# tricoreVCO.net
KiCad netlist of a schematic drawn in EAGLE
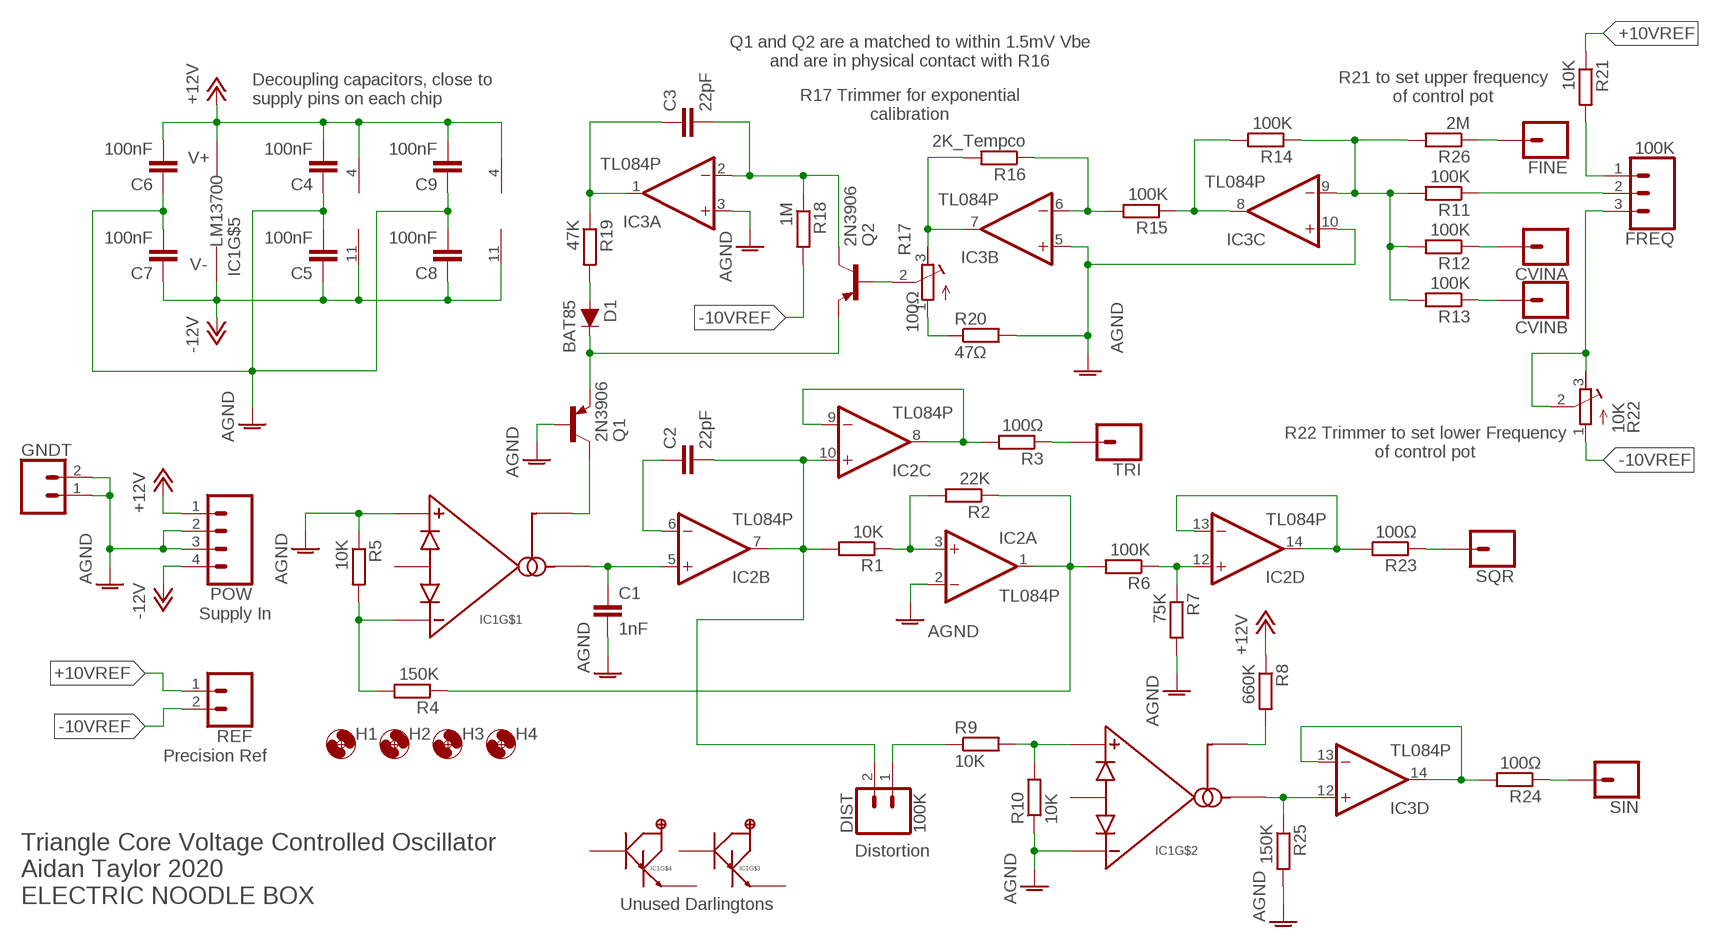
[diagram p0: schematic, sheet 1]

(export (version "E")
  (design (tool "Eeschema 10.0.6"))
  (components
    (comp (ref "C1")
      (value "1nF")
      (footprint "eagle-import:C050-025X075")
      (libsource (lib "eagle-import") (part "C-EU050-025X075"))
    )
    (comp (ref "C2")
      (value "22pF")
      (footprint "eagle-import:C050-025X075")
      (libsource (lib "eagle-import") (part "C-EU050-025X075"))
    )
    (comp (ref "C3")
      (value "22pF")
      (footprint "eagle-import:C050-025X075")
      (libsource (lib "eagle-import") (part "C-EU050-025X075"))
    )
    (comp (ref "C4")
      (value "100nF")
      (footprint "eagle-import:C050-025X075")
      (libsource (lib "eagle-import") (part "C-EU050-025X075"))
    )
    (comp (ref "C5")
      (value "100nF")
      (footprint "eagle-import:C050-025X075")
      (libsource (lib "eagle-import") (part "C-EU050-025X075"))
    )
    (comp (ref "C6")
      (value "100nF")
      (footprint "eagle-import:C050-025X075")
      (libsource (lib "eagle-import") (part "C-EU050-025X075"))
    )
    (comp (ref "C7")
      (value "100nF")
      (footprint "eagle-import:C050-025X075")
      (libsource (lib "eagle-import") (part "C-EU050-025X075"))
    )
    (comp (ref "C8")
      (value "100nF")
      (footprint "eagle-import:C050-025X075")
      (libsource (lib "eagle-import") (part "C-EU050-025X075"))
    )
    (comp (ref "C9")
      (value "100nF")
      (footprint "eagle-import:C050-025X075")
      (libsource (lib "eagle-import") (part "C-EU050-025X075"))
    )
    (comp (ref "CVINA")
      (value "CONN_01")
      (footprint "eagle-import:1X01")
      (libsource (lib "eagle-import") (part "CONN_01"))
    )
    (comp (ref "CVINB")
      (value "CONN_01")
      (footprint "eagle-import:1X01")
      (libsource (lib "eagle-import") (part "CONN_01"))
    )
    (comp (ref "D1")
      (value "BAT85")
      (footprint "eagle-import:DIODE-1N4148")
      (libsource (lib "eagle-import") (part "DIODE-1N4148"))
    )
    (comp (ref "DIST")
      (value "100K")
      (footprint "eagle-import:1X02")
      (libsource (lib "eagle-import") (part "CONN_02"))
    )
    (comp (ref "FINE")
      (value "CONN_01")
      (footprint "eagle-import:1X01")
      (libsource (lib "eagle-import") (part "CONN_01"))
    )
    (comp (ref "FREQ")
      (value "100K")
      (footprint "eagle-import:1X03")
      (libsource (lib "eagle-import") (part "CONN_03"))
    )
    (comp (ref "GNDT")
      (value "CONN_02")
      (footprint "eagle-import:1X02")
      (libsource (lib "eagle-import") (part "CONN_02"))
    )
    (comp (ref "H1")
      (value "MOUNT-HOLE3.2")
      (footprint "eagle-import:3,2")
      (libsource (lib "eagle-import") (part "MOUNT-HOLE3.2"))
    )
    (comp (ref "H2")
      (value "MOUNT-HOLE3.2")
      (footprint "eagle-import:3,2")
      (libsource (lib "eagle-import") (part "MOUNT-HOLE3.2"))
    )
    (comp (ref "H3")
      (value "MOUNT-HOLE3.2")
      (footprint "eagle-import:3,2")
      (libsource (lib "eagle-import") (part "MOUNT-HOLE3.2"))
    )
    (comp (ref "H4")
      (value "MOUNT-HOLE3.2")
      (footprint "eagle-import:3,2")
      (libsource (lib "eagle-import") (part "MOUNT-HOLE3.2"))
    )
    (comp (ref "IC1")
      (value "LM13700_DIP")
      (footprint "eagle-import:DIP16")
      (libsource (lib "eagle-import") (part "LM13700_DIP"))
    )
    (comp (ref "IC2")
      (value "TL084P")
      (footprint "eagle-import:DIL14")
      (libsource (lib "eagle-import") (part "TL084P"))
    )
    (comp (ref "IC3")
      (value "TL084P")
      (footprint "eagle-import:DIL14")
      (libsource (lib "eagle-import") (part "TL084P"))
    )
    (comp (ref "POW")
      (value "CONN_04POLAR")
      (footprint "eagle-import:MOLEX-1X4")
      (libsource (lib "eagle-import") (part "CONN_04POLAR"))
    )
    (comp (ref "Q1")
      (value "2N3906")
      (footprint "eagle-import:TO92")
      (libsource (lib "eagle-import") (part "2N3906"))
    )
    (comp (ref "Q2")
      (value "2N3906")
      (footprint "eagle-import:TO92")
      (libsource (lib "eagle-import") (part "2N3906"))
    )
    (comp (ref "R1")
      (value "10K")
      (footprint "eagle-import:0207_10")
      (libsource (lib "eagle-import") (part "R-EU_0207/10"))
    )
    (comp (ref "R2")
      (value "22K")
      (footprint "eagle-import:0207_10")
      (libsource (lib "eagle-import") (part "R-EU_0207/10"))
    )
    (comp (ref "R3")
      (value "100Ω")
      (footprint "eagle-import:0207_10")
      (libsource (lib "eagle-import") (part "R-EU_0207/10"))
    )
    (comp (ref "R4")
      (value "150K")
      (footprint "eagle-import:0207_10")
      (libsource (lib "eagle-import") (part "R-EU_0207/10"))
    )
    (comp (ref "R5")
      (value "10K")
      (footprint "eagle-import:0207_10")
      (libsource (lib "eagle-import") (part "R-EU_0207/10"))
    )
    (comp (ref "R6")
      (value "100K")
      (footprint "eagle-import:0207_10")
      (libsource (lib "eagle-import") (part "R-EU_0207/10"))
    )
    (comp (ref "R7")
      (value "75K")
      (footprint "eagle-import:0207_10")
      (libsource (lib "eagle-import") (part "R-EU_0207/10"))
    )
    (comp (ref "R8")
      (value "660K")
      (footprint "eagle-import:0207_10")
      (libsource (lib "eagle-import") (part "R-EU_0207/10"))
    )
    (comp (ref "R9")
      (value "10K")
      (footprint "eagle-import:0207_10")
      (libsource (lib "eagle-import") (part "R-EU_0207/10"))
    )
    (comp (ref "R10")
      (value "10K")
      (footprint "eagle-import:0207_10")
      (libsource (lib "eagle-import") (part "R-EU_0207/10"))
    )
    (comp (ref "R11")
      (value "100K")
      (footprint "eagle-import:0207_10")
      (libsource (lib "eagle-import") (part "R-EU_0207/10"))
    )
    (comp (ref "R12")
      (value "100K")
      (footprint "eagle-import:0207_10")
      (libsource (lib "eagle-import") (part "R-EU_0207/10"))
    )
    (comp (ref "R13")
      (value "100K")
      (footprint "eagle-import:0207_10")
      (libsource (lib "eagle-import") (part "R-EU_0207/10"))
    )
    (comp (ref "R14")
      (value "100K")
      (footprint "eagle-import:0207_10")
      (libsource (lib "eagle-import") (part "R-EU_0207/10"))
    )
    (comp (ref "R15")
      (value "100K")
      (footprint "eagle-import:0207_10")
      (libsource (lib "eagle-import") (part "R-EU_0207/10"))
    )
    (comp (ref "R16")
      (value "2K_Tempco")
      (footprint "eagle-import:0207_10")
      (libsource (lib "eagle-import") (part "R-EU_0207/10"))
    )
    (comp (ref "R17")
      (value "100Ω")
      (footprint "eagle-import:RTRIM3296W")
      (libsource (lib "eagle-import") (part "R-TRIMM3296W"))
    )
    (comp (ref "R18")
      (value "1M")
      (footprint "eagle-import:0207_10")
      (libsource (lib "eagle-import") (part "R-EU_0207/10"))
    )
    (comp (ref "R19")
      (value "47K")
      (footprint "eagle-import:0207_10")
      (libsource (lib "eagle-import") (part "R-EU_0207/10"))
    )
    (comp (ref "R20")
      (value "47Ω")
      (footprint "eagle-import:0207_10")
      (libsource (lib "eagle-import") (part "R-EU_0207/10"))
    )
    (comp (ref "R21")
      (value "10K")
      (footprint "eagle-import:0207_10")
      (libsource (lib "eagle-import") (part "R-EU_0207/10"))
    )
    (comp (ref "R22")
      (value "10K")
      (footprint "eagle-import:RTRIM3296W")
      (libsource (lib "eagle-import") (part "R-TRIMM3296W"))
    )
    (comp (ref "R23")
      (value "100Ω")
      (footprint "eagle-import:0207_10")
      (libsource (lib "eagle-import") (part "R-EU_0207/10"))
    )
    (comp (ref "R24")
      (value "100Ω")
      (footprint "eagle-import:0207_10")
      (libsource (lib "eagle-import") (part "R-EU_0207/10"))
    )
    (comp (ref "R25")
      (value "150K")
      (footprint "eagle-import:0207_10")
      (libsource (lib "eagle-import") (part "R-EU_0207/10"))
    )
    (comp (ref "R26")
      (value "2M")
      (footprint "eagle-import:0207_10")
      (libsource (lib "eagle-import") (part "R-EU_0207/10"))
    )
    (comp (ref "REF")
      (value "CONN_02POLAR")
      (footprint "eagle-import:MOLEX-1X2")
      (libsource (lib "eagle-import") (part "CONN_02POLAR"))
    )
    (comp (ref "SIN")
      (value "CONN_01")
      (footprint "eagle-import:1X01")
      (libsource (lib "eagle-import") (part "CONN_01"))
    )
    (comp (ref "SQR")
      (value "CONN_01")
      (footprint "eagle-import:1X01")
      (libsource (lib "eagle-import") (part "CONN_01"))
    )
    (comp (ref "TRI")
      (value "CONN_01")
      (footprint "eagle-import:1X01")
      (libsource (lib "eagle-import") (part "CONN_01"))
    )
  )
  (nets
    (net (code "1") (name "+10VREF") (class "Default")
      (node (ref "R21") (pin "1") (pinfunction "1_1") (pintype "passive"))
      (node (ref "REF") (pin "1") (pinfunction "1_1") (pintype "passive"))
    )
    (net (code "2") (name "+12V") (class "Default")
      (node (ref "C4") (pin "2") (pinfunction "2_2") (pintype "passive"))
      (node (ref "C6") (pin "2") (pinfunction "2_2") (pintype "passive"))
      (node (ref "C9") (pin "2") (pinfunction "2_2") (pintype "passive"))
      (node (ref "IC1") (pin "11") (pinfunction "V+_11") (pintype "power_in"))
      (node (ref "IC2") (pin "4") (pinfunction "V+_4") (pintype "power_in"))
      (node (ref "IC3") (pin "4") (pinfunction "V+_4") (pintype "power_in"))
      (node (ref "POW") (pin "1") (pinfunction "1_1") (pintype "passive"))
      (node (ref "R8") (pin "1") (pinfunction "1_1") (pintype "passive"))
    )
    (net (code "3") (name "-10VREF") (class "Default")
      (node (ref "R18") (pin "2") (pinfunction "2_2") (pintype "passive"))
      (node (ref "R22") (pin "1") (pinfunction "A_1") (pintype "passive"))
      (node (ref "REF") (pin "2") (pinfunction "2_2") (pintype "passive"))
    )
    (net (code "4") (name "-12V") (class "Default")
      (node (ref "C5") (pin "1") (pinfunction "1_1") (pintype "passive"))
      (node (ref "C7") (pin "1") (pinfunction "1_1") (pintype "passive"))
      (node (ref "C8") (pin "1") (pinfunction "1_1") (pintype "passive"))
      (node (ref "IC1") (pin "6") (pinfunction "V-_6") (pintype "power_in"))
      (node (ref "IC2") (pin "11") (pinfunction "V-_11") (pintype "power_in"))
      (node (ref "IC3") (pin "11") (pinfunction "V-_11") (pintype "power_in"))
      (node (ref "POW") (pin "4") (pinfunction "4_4") (pintype "passive"))
    )
    (net (code "5") (name "AGND") (class "Default")
      (node (ref "C1") (pin "2") (pinfunction "2_2") (pintype "passive"))
      (node (ref "C4") (pin "1") (pinfunction "1_1") (pintype "passive"))
      (node (ref "C5") (pin "2") (pinfunction "2_2") (pintype "passive"))
      (node (ref "C6") (pin "1") (pinfunction "1_1") (pintype "passive"))
      (node (ref "C7") (pin "2") (pinfunction "2_2") (pintype "passive"))
      (node (ref "C8") (pin "2") (pinfunction "2_2") (pintype "passive"))
      (node (ref "C9") (pin "1") (pinfunction "1_1") (pintype "passive"))
      (node (ref "GNDT") (pin "1") (pinfunction "1_1") (pintype "passive"))
      (node (ref "GNDT") (pin "2") (pinfunction "2_2") (pintype "passive"))
      (node (ref "IC1") (pin "13") (pinfunction "AMP-_13") (pintype "input"))
      (node (ref "IC1") (pin "3") (pinfunction "AMP+_3") (pintype "input"))
      (node (ref "IC2") (pin "2") (pinfunction "-IN_2") (pintype "input"))
      (node (ref "IC3") (pin "10") (pinfunction "+IN_10") (pintype "input"))
      (node (ref "IC3") (pin "3") (pinfunction "+IN_3") (pintype "input"))
      (node (ref "IC3") (pin "5") (pinfunction "+IN_5") (pintype "input"))
      (node (ref "POW") (pin "2") (pinfunction "2_2") (pintype "passive"))
      (node (ref "POW") (pin "3") (pinfunction "3_3") (pintype "passive"))
      (node (ref "Q1") (pin "2") (pinfunction "B_2") (pintype "passive"))
      (node (ref "R10") (pin "1") (pinfunction "1_1") (pintype "passive"))
      (node (ref "R20") (pin "2") (pinfunction "2_2") (pintype "passive"))
      (node (ref "R25") (pin "2") (pinfunction "2_2") (pintype "passive"))
      (node (ref "R5") (pin "1") (pinfunction "1_1") (pintype "passive"))
      (node (ref "R7") (pin "2") (pinfunction "2_2") (pintype "passive"))
    )
    (net (code "6") (name "Net-(CVINA-Pad1)") (class "Default")
      (node (ref "CVINA") (pin "1") (pinfunction "1_1") (pintype "passive"))
      (node (ref "R12") (pin "1") (pinfunction "1_1") (pintype "passive"))
    )
    (net (code "7") (name "Net-(CVINB-Pad1)") (class "Default")
      (node (ref "CVINB") (pin "1") (pinfunction "1_1") (pintype "passive"))
      (node (ref "R13") (pin "1") (pinfunction "1_1") (pintype "passive"))
    )
    (net (code "8") (name "Net-(D1-PadA)") (class "Default")
      (node (ref "D1") (pin "A") (pinfunction "A_A") (pintype "passive"))
      (node (ref "R19") (pin "2") (pinfunction "2_2") (pintype "passive"))
    )
    (net (code "9") (name "Net-(DIST-Pad1)") (class "Default")
      (node (ref "DIST") (pin "1") (pinfunction "1_1") (pintype "passive"))
      (node (ref "R9") (pin "1") (pinfunction "1_1") (pintype "passive"))
    )
    (net (code "10") (name "Net-(FINE-Pad1)") (class "Default")
      (node (ref "FINE") (pin "1") (pinfunction "1_1") (pintype "passive"))
      (node (ref "R26") (pin "1") (pinfunction "1_1") (pintype "passive"))
    )
    (net (code "11") (name "Net-(FREQ-Pad1)") (class "Default")
      (node (ref "FREQ") (pin "1") (pinfunction "1_1") (pintype "passive"))
      (node (ref "R21") (pin "2") (pinfunction "2_2") (pintype "passive"))
    )
    (net (code "12") (name "Net-(FREQ-Pad2)") (class "Default")
      (node (ref "FREQ") (pin "2") (pinfunction "2_2") (pintype "passive"))
      (node (ref "R11") (pin "1") (pinfunction "1_1") (pintype "passive"))
    )
    (net (code "13") (name "Net-(IC1A-AMP-)") (class "Default")
      (node (ref "IC1") (pin "4") (pinfunction "AMP-_4") (pintype "input"))
      (node (ref "R4") (pin "2") (pinfunction "2_2") (pintype "passive"))
      (node (ref "R5") (pin "2") (pinfunction "2_2") (pintype "passive"))
    )
    (net (code "14") (name "Net-(IC1A-AMPBIAS)") (class "Default")
      (node (ref "IC1") (pin "1") (pinfunction "AMPBIAS_1") (pintype "input"))
      (node (ref "Q1") (pin "1") (pinfunction "C_1") (pintype "passive"))
    )
    (net (code "15") (name "Net-(IC1A-AMPOUT)") (class "Default")
      (node (ref "C1") (pin "1") (pinfunction "1_1") (pintype "passive"))
      (node (ref "IC1") (pin "5") (pinfunction "AMPOUT_5") (pintype "output"))
      (node (ref "IC2") (pin "5") (pinfunction "+IN_5") (pintype "input"))
    )
    (net (code "16") (name "Net-(IC1B-AMP+)") (class "Default")
      (node (ref "IC1") (pin "14") (pinfunction "AMP+_14") (pintype "input"))
      (node (ref "R10") (pin "2") (pinfunction "2_2") (pintype "passive"))
      (node (ref "R9") (pin "2") (pinfunction "2_2") (pintype "passive"))
    )
    (net (code "17") (name "Net-(IC1B-AMPBIAS)") (class "Default")
      (node (ref "IC1") (pin "16") (pinfunction "AMPBIAS_16") (pintype "input"))
      (node (ref "R8") (pin "2") (pinfunction "2_2") (pintype "passive"))
    )
    (net (code "18") (name "Net-(IC1B-AMPOUT)") (class "Default")
      (node (ref "IC1") (pin "12") (pinfunction "AMPOUT_12") (pintype "output"))
      (node (ref "IC3") (pin "12") (pinfunction "+IN_12") (pintype "input"))
      (node (ref "R25") (pin "1") (pinfunction "1_1") (pintype "passive"))
    )
    (net (code "19") (name "Net-(IC2A-+IN)") (class "Default")
      (node (ref "IC2") (pin "3") (pinfunction "+IN_3") (pintype "input"))
      (node (ref "R1") (pin "1") (pinfunction "1_1") (pintype "passive"))
      (node (ref "R2") (pin "2") (pinfunction "2_2") (pintype "passive"))
    )
    (net (code "20") (name "Net-(IC2A-OUT)") (class "Default")
      (node (ref "IC2") (pin "1") (pinfunction "OUT_1") (pintype "output"))
      (node (ref "R2") (pin "1") (pinfunction "1_1") (pintype "passive"))
      (node (ref "R4") (pin "1") (pinfunction "1_1") (pintype "passive"))
      (node (ref "R6") (pin "2") (pinfunction "2_2") (pintype "passive"))
    )
    (net (code "21") (name "Net-(IC2B--IN)") (class "Default")
      (node (ref "C2") (pin "1") (pinfunction "1_1") (pintype "passive"))
      (node (ref "IC2") (pin "6") (pinfunction "-IN_6") (pintype "input"))
    )
    (net (code "22") (name "Net-(IC2B-OUT)") (class "Default")
      (node (ref "C2") (pin "2") (pinfunction "2_2") (pintype "passive"))
      (node (ref "DIST") (pin "2") (pinfunction "2_2") (pintype "passive"))
      (node (ref "IC2") (pin "10") (pinfunction "+IN_10") (pintype "input"))
      (node (ref "IC2") (pin "7") (pinfunction "OUT_7") (pintype "output"))
      (node (ref "R1") (pin "2") (pinfunction "2_2") (pintype "passive"))
    )
    (net (code "23") (name "Net-(IC2C--IN)") (class "Default")
      (node (ref "IC2") (pin "8") (pinfunction "OUT_8") (pintype "output"))
      (node (ref "IC2") (pin "9") (pinfunction "-IN_9") (pintype "input"))
      (node (ref "R3") (pin "2") (pinfunction "2_2") (pintype "passive"))
    )
    (net (code "24") (name "Net-(IC2D-+IN)") (class "Default")
      (node (ref "IC2") (pin "12") (pinfunction "+IN_12") (pintype "input"))
      (node (ref "R6") (pin "1") (pinfunction "1_1") (pintype "passive"))
      (node (ref "R7") (pin "1") (pinfunction "1_1") (pintype "passive"))
    )
    (net (code "25") (name "Net-(IC2D--IN)") (class "Default")
      (node (ref "IC2") (pin "13") (pinfunction "-IN_13") (pintype "input"))
      (node (ref "IC2") (pin "14") (pinfunction "OUT_14") (pintype "output"))
      (node (ref "R23") (pin "2") (pinfunction "2_2") (pintype "passive"))
    )
    (net (code "26") (name "Net-(IC3A--IN)") (class "Default")
      (node (ref "C3") (pin "2") (pinfunction "2_2") (pintype "passive"))
      (node (ref "IC3") (pin "2") (pinfunction "-IN_2") (pintype "input"))
      (node (ref "Q2") (pin "1") (pinfunction "C_1") (pintype "passive"))
      (node (ref "R18") (pin "1") (pinfunction "1_1") (pintype "passive"))
    )
    (net (code "27") (name "Net-(IC3A-OUT)") (class "Default")
      (node (ref "C3") (pin "1") (pinfunction "1_1") (pintype "passive"))
      (node (ref "IC3") (pin "1") (pinfunction "OUT_1") (pintype "output"))
      (node (ref "R19") (pin "1") (pinfunction "1_1") (pintype "passive"))
    )
    (net (code "28") (name "Net-(IC3B--IN)") (class "Default")
      (node (ref "IC3") (pin "6") (pinfunction "-IN_6") (pintype "input"))
      (node (ref "R15") (pin "2") (pinfunction "2_2") (pintype "passive"))
      (node (ref "R16") (pin "1") (pinfunction "1_1") (pintype "passive"))
    )
    (net (code "29") (name "Net-(IC3B-OUT)") (class "Default")
      (node (ref "IC3") (pin "7") (pinfunction "OUT_7") (pintype "output"))
      (node (ref "R16") (pin "2") (pinfunction "2_2") (pintype "passive"))
      (node (ref "R17") (pin "3") (pinfunction "E_3") (pintype "passive"))
    )
    (net (code "30") (name "Net-(IC3C--IN)") (class "Default")
      (node (ref "IC3") (pin "9") (pinfunction "-IN_9") (pintype "input"))
      (node (ref "R11") (pin "2") (pinfunction "2_2") (pintype "passive"))
      (node (ref "R12") (pin "2") (pinfunction "2_2") (pintype "passive"))
      (node (ref "R13") (pin "2") (pinfunction "2_2") (pintype "passive"))
      (node (ref "R14") (pin "1") (pinfunction "1_1") (pintype "passive"))
      (node (ref "R26") (pin "2") (pinfunction "2_2") (pintype "passive"))
    )
    (net (code "31") (name "Net-(IC3C-OUT)") (class "Default")
      (node (ref "IC3") (pin "8") (pinfunction "OUT_8") (pintype "output"))
      (node (ref "R14") (pin "2") (pinfunction "2_2") (pintype "passive"))
      (node (ref "R15") (pin "1") (pinfunction "1_1") (pintype "passive"))
    )
    (net (code "32") (name "Net-(IC3D--IN)") (class "Default")
      (node (ref "IC3") (pin "13") (pinfunction "-IN_13") (pintype "input"))
      (node (ref "IC3") (pin "14") (pinfunction "OUT_14") (pintype "output"))
      (node (ref "R24") (pin "2") (pinfunction "2_2") (pintype "passive"))
    )
    (net (code "33") (name "Net-(Q1-E)") (class "Default")
      (node (ref "D1") (pin "C") (pinfunction "C_C") (pintype "passive"))
      (node (ref "Q1") (pin "3") (pinfunction "E_3") (pintype "passive"))
      (node (ref "Q2") (pin "3") (pinfunction "E_3") (pintype "passive"))
    )
    (net (code "34") (name "Net-(Q2-B)") (class "Default")
      (node (ref "Q2") (pin "2") (pinfunction "B_2") (pintype "passive"))
      (node (ref "R17") (pin "2") (pinfunction "S_2") (pintype "passive"))
    )
    (net (code "35") (name "Net-(R3-Pad1)") (class "Default")
      (node (ref "R3") (pin "1") (pinfunction "1_1") (pintype "passive"))
      (node (ref "TRI") (pin "1") (pinfunction "1_1") (pintype "passive"))
    )
    (net (code "36") (name "Net-(R17-A)") (class "Default")
      (node (ref "R17") (pin "1") (pinfunction "A_1") (pintype "passive"))
      (node (ref "R20") (pin "1") (pinfunction "1_1") (pintype "passive"))
    )
    (net (code "37") (name "Net-(R22-E)") (class "Default")
      (node (ref "FREQ") (pin "3") (pinfunction "3_3") (pintype "passive"))
      (node (ref "R22") (pin "2") (pinfunction "S_2") (pintype "passive"))
      (node (ref "R22") (pin "3") (pinfunction "E_3") (pintype "passive"))
    )
    (net (code "38") (name "Net-(R23-Pad1)") (class "Default")
      (node (ref "R23") (pin "1") (pinfunction "1_1") (pintype "passive"))
      (node (ref "SQR") (pin "1") (pinfunction "1_1") (pintype "passive"))
    )
    (net (code "39") (name "Net-(R24-Pad1)") (class "Default")
      (node (ref "R24") (pin "1") (pinfunction "1_1") (pintype "passive"))
      (node (ref "SIN") (pin "1") (pinfunction "1_1") (pintype "passive"))
    )
    (net (code "40") (name "unconnected-(IC1A-DIODES-Pad2)") (class "Default")
      (node (ref "IC1") (pin "2") (pinfunction "DIODES_2") (pintype "input"))
    )
    (net (code "41") (name "unconnected-(IC1B-DIODES-Pad15)") (class "Default")
      (node (ref "IC1") (pin "15") (pinfunction "DIODES_15") (pintype "input"))
    )
    (net (code "42") (name "unconnected-(IC1C-BUFF_IN-Pad7)") (class "Default")
      (node (ref "IC1") (pin "7") (pinfunction "BUFF_IN_7") (pintype "input"))
    )
    (net (code "43") (name "unconnected-(IC1C-BUFF_OUT-Pad8)") (class "Default")
      (node (ref "IC1") (pin "8") (pinfunction "BUFF_OUT_8") (pintype "bidirectional"))
    )
    (net (code "44") (name "unconnected-(IC1D-BUFF_IN-Pad10)") (class "Default")
      (node (ref "IC1") (pin "10") (pinfunction "BUFF_IN_10") (pintype "input"))
    )
    (net (code "45") (name "unconnected-(IC1D-BUFF_OUT-Pad9)") (class "Default")
      (node (ref "IC1") (pin "9") (pinfunction "BUFF_OUT_9") (pintype "bidirectional"))
    )
  )
)
